# Display.net
KiCad netlist of a schematic drawn in Altium Designer
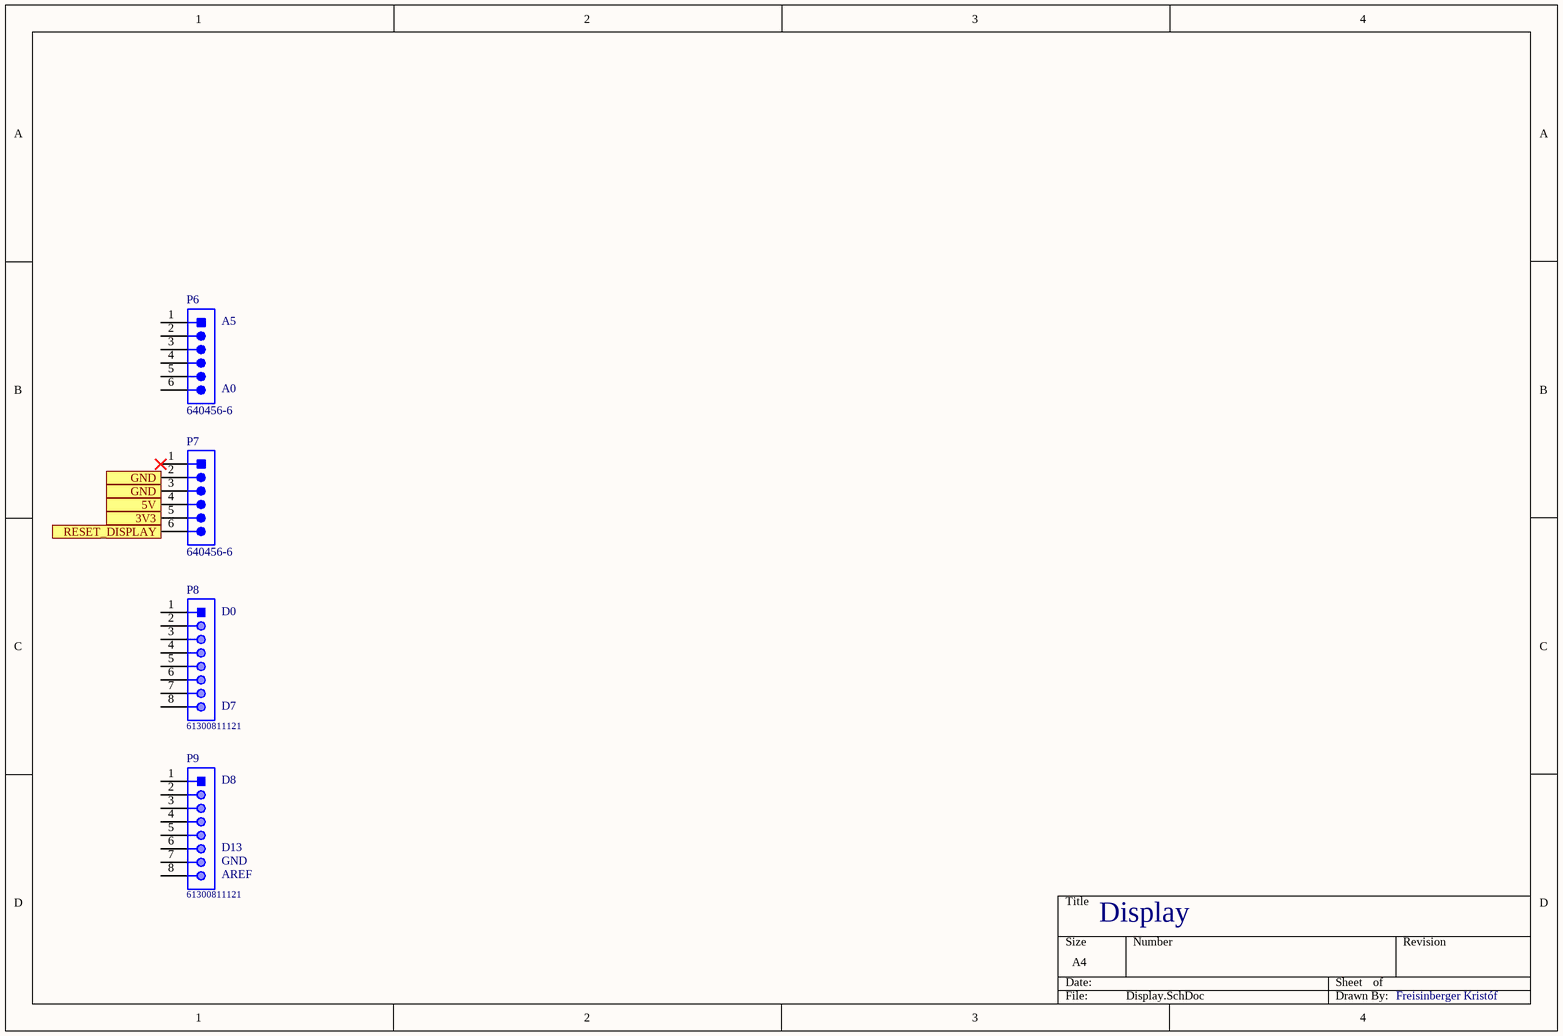
[diagram p0: Display.SchDoc]

(export (version "E")
  (design (tool "Eeschema 10.0.6"))
  (components
    (comp (ref "P6")
      (value "640456-6")
      (footprint "TECO-640456-6_V")
      (fields (field (name "MANUFACTURER") "TE Connectivity"))
      (libsource (lib "Altium Content Vault") (part "CN-1P-M-R6"))
    )
    (comp (ref "P7")
      (value "640456-6")
      (footprint "TECO-640456-6_V")
      (fields (field (name "MANUFACTURER") "TE Connectivity"))
      (libsource (lib "Altium Content Vault") (part "CN-1P-M-R6"))
    )
    (comp (ref "P8")
      (value "61300811121")
      (footprint "61300811121")
      (description "THT Vertical Pin Header WR-PHD, Pitch 2.54 mm, Single Row, 8 pins")
      (fields (field (name "MANUFACTURER") "Wurth Elektronik") (field (name "PUBLISHER") "WurthElektronik"))
      (libsource (lib "Altium Content Vault") (part "WE-CN-1P-M-R8"))
    )
    (comp (ref "P9")
      (value "61300811121")
      (footprint "61300811121")
      (description "THT Vertical Pin Header WR-PHD, Pitch 2.54 mm, Single Row, 8 pins")
      (fields (field (name "MANUFACTURER") "Wurth Elektronik") (field (name "PUBLISHER") "WurthElektronik"))
      (libsource (lib "Altium Content Vault") (part "WE-CN-1P-M-R8"))
    )
  )
  (nets
    (net (code "1") (name "/3V3") (class "Default")
      (node (ref "P7") (pin "5") (pinfunction "5_5") (pintype "passive"))
    )
    (net (code "2") (name "/5V") (class "Default")
      (node (ref "P7") (pin "4") (pinfunction "4_4") (pintype "passive"))
    )
    (net (code "3") (name "/GND") (class "Default")
      (node (ref "P7") (pin "2") (pinfunction "2_2") (pintype "passive"))
      (node (ref "P7") (pin "3") (pinfunction "3_3") (pintype "passive"))
    )
    (net (code "4") (name "/RESET_DISPLAY") (class "Default")
      (node (ref "P7") (pin "6") (pinfunction "6_6") (pintype "passive"))
    )
    (net (code "5") (name "unconnected-(P6-Pad1)") (class "Default")
      (node (ref "P6") (pin "1") (pinfunction "1_1") (pintype "passive"))
    )
    (net (code "6") (name "unconnected-(P6-Pad2)") (class "Default")
      (node (ref "P6") (pin "2") (pinfunction "2_2") (pintype "passive"))
    )
    (net (code "7") (name "unconnected-(P6-Pad3)") (class "Default")
      (node (ref "P6") (pin "3") (pinfunction "3_3") (pintype "passive"))
    )
    (net (code "8") (name "unconnected-(P6-Pad4)") (class "Default")
      (node (ref "P6") (pin "4") (pinfunction "4_4") (pintype "passive"))
    )
    (net (code "9") (name "unconnected-(P6-Pad5)") (class "Default")
      (node (ref "P6") (pin "5") (pinfunction "5_5") (pintype "passive"))
    )
    (net (code "10") (name "unconnected-(P6-Pad6)") (class "Default")
      (node (ref "P6") (pin "6") (pinfunction "6_6") (pintype "passive"))
    )
    (net (code "11") (name "unconnected-(P7-Pad1)") (class "Default")
      (node (ref "P7") (pin "1") (pinfunction "1_1") (pintype "passive+no_connect"))
    )
    (net (code "12") (name "unconnected-(P8-Pad1)") (class "Default")
      (node (ref "P8") (pin "1") (pinfunction "1_1") (pintype "passive"))
    )
    (net (code "13") (name "unconnected-(P8-Pad2)") (class "Default")
      (node (ref "P8") (pin "2") (pinfunction "2_2") (pintype "passive"))
    )
    (net (code "14") (name "unconnected-(P8-Pad3)") (class "Default")
      (node (ref "P8") (pin "3") (pinfunction "3_3") (pintype "passive"))
    )
    (net (code "15") (name "unconnected-(P8-Pad4)") (class "Default")
      (node (ref "P8") (pin "4") (pinfunction "4_4") (pintype "passive"))
    )
    (net (code "16") (name "unconnected-(P8-Pad5)") (class "Default")
      (node (ref "P8") (pin "5") (pinfunction "5_5") (pintype "passive"))
    )
    (net (code "17") (name "unconnected-(P8-Pad6)") (class "Default")
      (node (ref "P8") (pin "6") (pinfunction "6_6") (pintype "passive"))
    )
    (net (code "18") (name "unconnected-(P8-Pad7)") (class "Default")
      (node (ref "P8") (pin "7") (pinfunction "7_7") (pintype "passive"))
    )
    (net (code "19") (name "unconnected-(P8-Pad8)") (class "Default")
      (node (ref "P8") (pin "8") (pinfunction "8_8") (pintype "passive"))
    )
    (net (code "20") (name "unconnected-(P9-Pad1)") (class "Default")
      (node (ref "P9") (pin "1") (pinfunction "1_1") (pintype "passive"))
    )
    (net (code "21") (name "unconnected-(P9-Pad2)") (class "Default")
      (node (ref "P9") (pin "2") (pinfunction "2_2") (pintype "passive"))
    )
    (net (code "22") (name "unconnected-(P9-Pad3)") (class "Default")
      (node (ref "P9") (pin "3") (pinfunction "3_3") (pintype "passive"))
    )
    (net (code "23") (name "unconnected-(P9-Pad4)") (class "Default")
      (node (ref "P9") (pin "4") (pinfunction "4_4") (pintype "passive"))
    )
    (net (code "24") (name "unconnected-(P9-Pad5)") (class "Default")
      (node (ref "P9") (pin "5") (pinfunction "5_5") (pintype "passive"))
    )
    (net (code "25") (name "unconnected-(P9-Pad6)") (class "Default")
      (node (ref "P9") (pin "6") (pinfunction "6_6") (pintype "passive"))
    )
    (net (code "26") (name "unconnected-(P9-Pad7)") (class "Default")
      (node (ref "P9") (pin "7") (pinfunction "7_7") (pintype "passive"))
    )
    (net (code "27") (name "unconnected-(P9-Pad8)") (class "Default")
      (node (ref "P9") (pin "8") (pinfunction "8_8") (pintype "passive"))
    )
  )
)
